# screwshield-v1_0.net
KiCad netlist of a schematic drawn in EAGLE
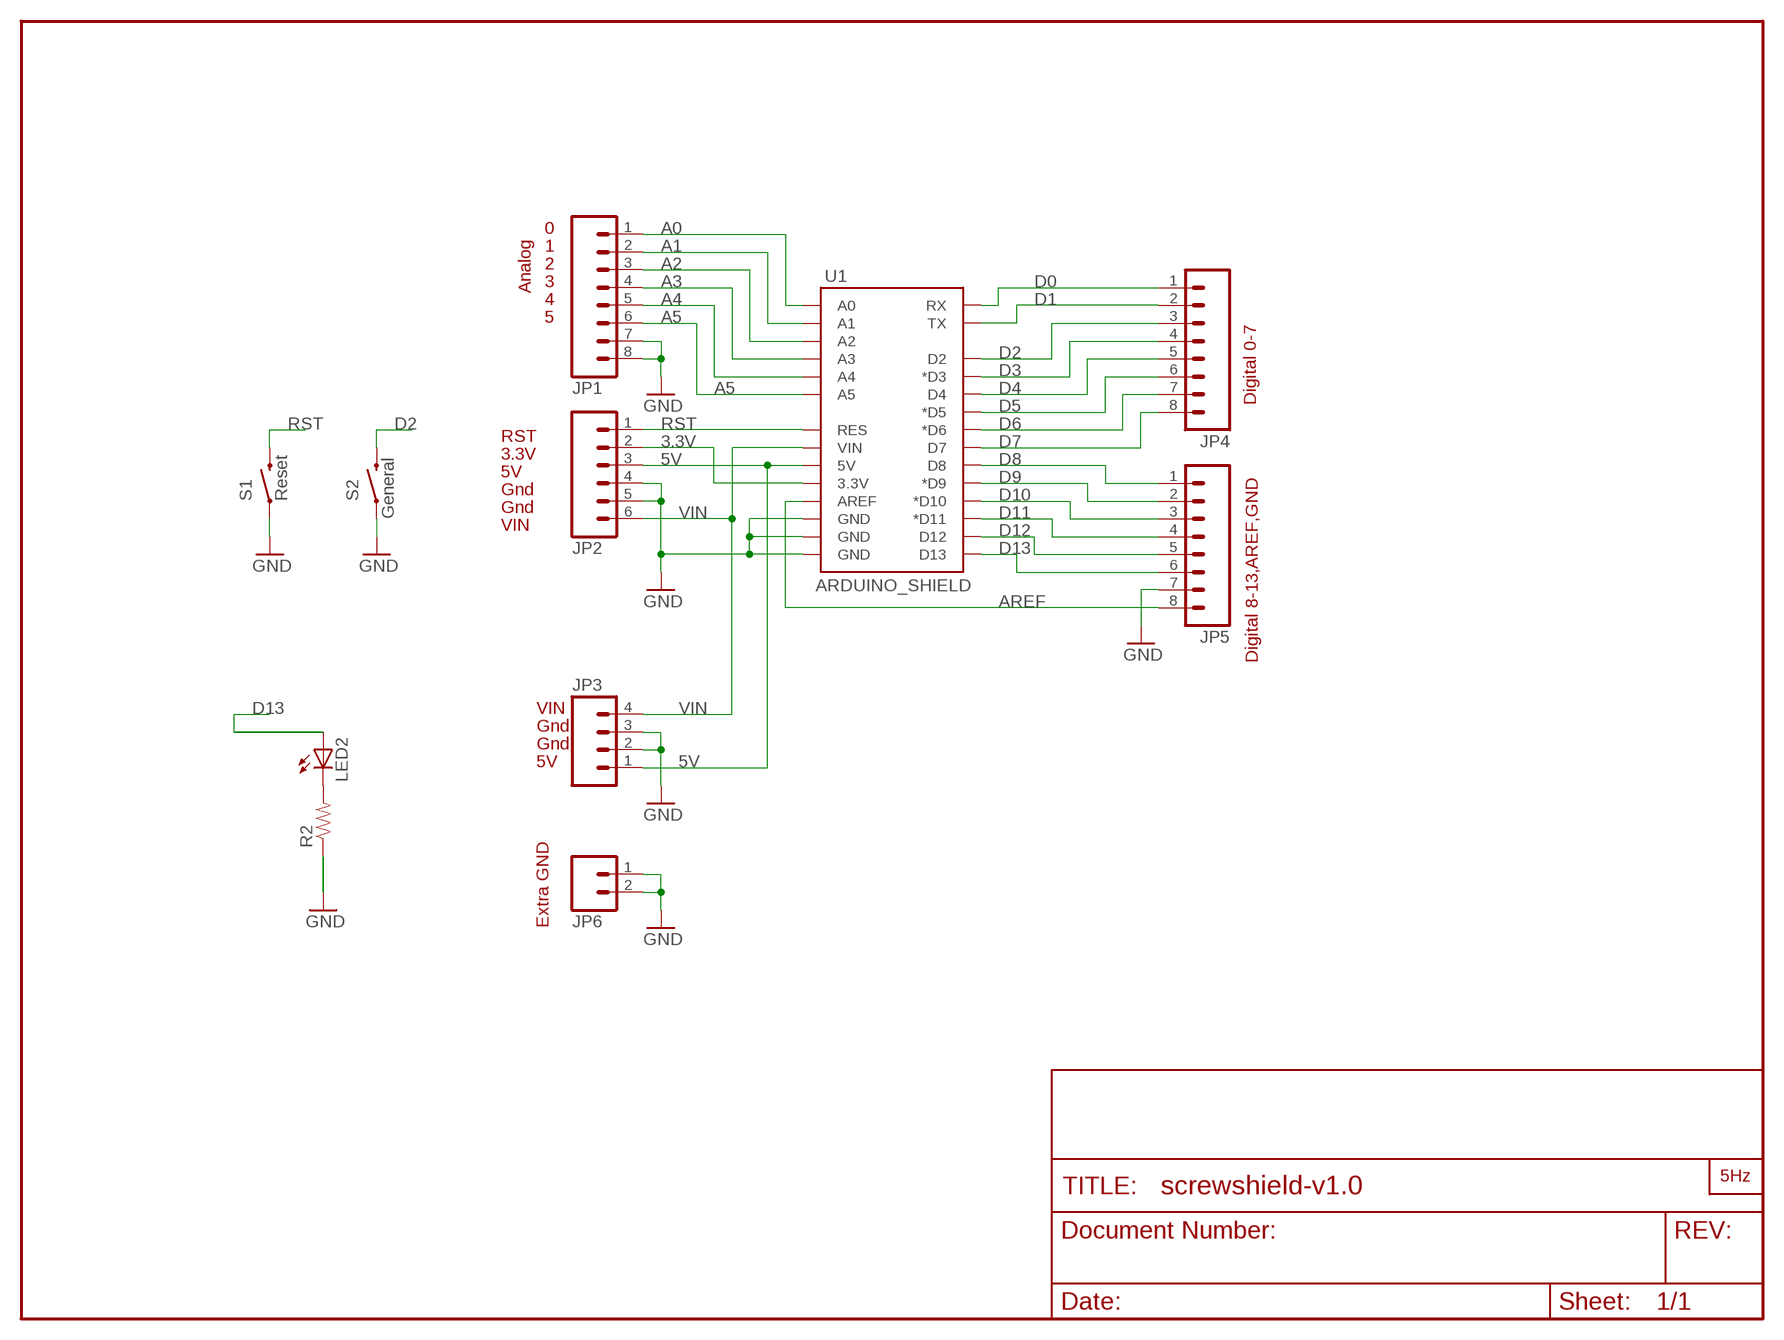
[diagram p0: schematic, sheet 1]

(export (version "E")
  (design (tool "Eeschema 10.0.6"))
  (components
    (comp (ref "JP1")
      (value "M083.5MM-8")
      (footprint "eagle-import:SCREWTERMINAL-3.5MM-8")
      (libsource (lib "eagle-import") (part "M083.5MM-8"))
    )
    (comp (ref "JP2")
      (value "M063.5MM-6")
      (footprint "eagle-import:SCREWTERMINAL-3.5MM-6")
      (libsource (lib "eagle-import") (part "M063.5MM-6"))
    )
    (comp (ref "JP3")
      (value "M04SCREW")
      (footprint "eagle-import:SCREWTERMINAL-3.5MM-4")
      (libsource (lib "eagle-import") (part "M04SCREW"))
    )
    (comp (ref "JP4")
      (value "M083.5MM-8")
      (footprint "eagle-import:SCREWTERMINAL-3.5MM-8")
      (libsource (lib "eagle-import") (part "M083.5MM-8"))
    )
    (comp (ref "JP5")
      (value "M083.5MM-8")
      (footprint "eagle-import:SCREWTERMINAL-3.5MM-8")
      (libsource (lib "eagle-import") (part "M083.5MM-8"))
    )
    (comp (ref "JP6")
      (value "M023.5MM")
      (footprint "eagle-import:SCREWTERMINAL-3.5MM-2")
      (libsource (lib "eagle-import") (part "M023.5MM"))
    )
    (comp (ref "LED2")
      (value "LED0603")
      (footprint "eagle-import:LED-0603")
      (libsource (lib "eagle-import") (part "LED0603"))
    )
    (comp (ref "R2")
      (value "RESISTOR0603-RES")
      (footprint "eagle-import:0603-RES")
      (libsource (lib "eagle-import") (part "RESISTOR0603-RES"))
    )
    (comp (ref "S1")
      (value "Reset")
      (footprint "eagle-import:TACTILE-PTH")
      (libsource (lib "eagle-import") (part "SWITCH-MOMENTARY-2PTH"))
    )
    (comp (ref "S2")
      (value "General")
      (footprint "eagle-import:TACTILE-PTH")
      (libsource (lib "eagle-import") (part "SWITCH-MOMENTARY-2PTH"))
    )
    (comp (ref "U$1")
      (value "LOGO_SILKL15MM")
      (footprint "eagle-import:LARGO_15MM")
      (libsource (lib "eagle-import") (part "LOGO_SILKL15MM"))
    )
    (comp (ref "U1")
      (value "ARDUINO_SHIELD")
      (footprint "eagle-import:DUEMILANOVE_SHIELD_NOHOLES")
      (libsource (lib "eagle-import") (part "ARDUINO_SHIELDNOHOLES"))
    )
  )
  (nets
    (net (code "1") (name "/3.3V") (class "Default")
      (node (ref "JP2") (pin "2") (pinfunction "2_2") (pintype "passive"))
      (node (ref "U1") (pin "3.3V") (pinfunction "3.3V_3.3V") (pintype "bidirectional"))
    )
    (net (code "2") (name "/5V") (class "Default")
      (node (ref "JP2") (pin "3") (pinfunction "3_3") (pintype "passive"))
      (node (ref "JP3") (pin "1") (pinfunction "1_1") (pintype "passive"))
      (node (ref "U1") (pin "5V") (pinfunction "5V_5V") (pintype "bidirectional"))
    )
    (net (code "3") (name "/A0") (class "Default")
      (node (ref "JP1") (pin "1") (pinfunction "1_1") (pintype "passive"))
      (node (ref "U1") (pin "A0") (pinfunction "A0_A0") (pintype "bidirectional"))
    )
    (net (code "4") (name "/A1") (class "Default")
      (node (ref "JP1") (pin "2") (pinfunction "2_2") (pintype "passive"))
      (node (ref "U1") (pin "A1") (pinfunction "A1_A1") (pintype "bidirectional"))
    )
    (net (code "5") (name "/A2") (class "Default")
      (node (ref "JP1") (pin "3") (pinfunction "3_3") (pintype "passive"))
      (node (ref "U1") (pin "A2") (pinfunction "A2_A2") (pintype "bidirectional"))
    )
    (net (code "6") (name "/A3") (class "Default")
      (node (ref "JP1") (pin "4") (pinfunction "4_4") (pintype "passive"))
      (node (ref "U1") (pin "A3") (pinfunction "A3_A3") (pintype "bidirectional"))
    )
    (net (code "7") (name "/A4") (class "Default")
      (node (ref "JP1") (pin "5") (pinfunction "5_5") (pintype "passive"))
      (node (ref "U1") (pin "A4") (pinfunction "A4_A4") (pintype "bidirectional"))
    )
    (net (code "8") (name "/A5") (class "Default")
      (node (ref "JP1") (pin "6") (pinfunction "6_6") (pintype "passive"))
      (node (ref "U1") (pin "A5") (pinfunction "A5_A5") (pintype "bidirectional"))
    )
    (net (code "9") (name "/AREF") (class "Default")
      (node (ref "JP5") (pin "8") (pinfunction "8_8") (pintype "passive"))
      (node (ref "U1") (pin "AREF") (pinfunction "AREF_AREF") (pintype "bidirectional"))
    )
    (net (code "10") (name "/D0") (class "Default")
      (node (ref "JP4") (pin "1") (pinfunction "1_1") (pintype "passive"))
      (node (ref "U1") (pin "RX") (pinfunction "RX_RX") (pintype "bidirectional"))
    )
    (net (code "11") (name "/D1") (class "Default")
      (node (ref "JP4") (pin "2") (pinfunction "2_2") (pintype "passive"))
      (node (ref "U1") (pin "TX") (pinfunction "TX_TX") (pintype "bidirectional"))
    )
    (net (code "12") (name "/D2") (class "Default")
      (node (ref "JP4") (pin "3") (pinfunction "3_3") (pintype "passive"))
      (node (ref "S2") (pin "3") (pinfunction "2_3") (pintype "passive"))
      (node (ref "U1") (pin "D2") (pinfunction "D2_D2") (pintype "bidirectional"))
    )
    (net (code "13") (name "/D3") (class "Default")
      (node (ref "JP4") (pin "4") (pinfunction "4_4") (pintype "passive"))
      (node (ref "U1") (pin "D3") (pinfunction "*D3_D3") (pintype "bidirectional"))
    )
    (net (code "14") (name "/D4") (class "Default")
      (node (ref "JP4") (pin "5") (pinfunction "5_5") (pintype "passive"))
      (node (ref "U1") (pin "D4") (pinfunction "D4_D4") (pintype "bidirectional"))
    )
    (net (code "15") (name "/D5") (class "Default")
      (node (ref "JP4") (pin "6") (pinfunction "6_6") (pintype "passive"))
      (node (ref "U1") (pin "D5") (pinfunction "*D5_D5") (pintype "bidirectional"))
    )
    (net (code "16") (name "/D6") (class "Default")
      (node (ref "JP4") (pin "7") (pinfunction "7_7") (pintype "passive"))
      (node (ref "U1") (pin "D6") (pinfunction "*D6_D6") (pintype "bidirectional"))
    )
    (net (code "17") (name "/D7") (class "Default")
      (node (ref "JP4") (pin "8") (pinfunction "8_8") (pintype "passive"))
      (node (ref "U1") (pin "D7") (pinfunction "D7_D7") (pintype "bidirectional"))
    )
    (net (code "18") (name "/D8") (class "Default")
      (node (ref "JP5") (pin "1") (pinfunction "1_1") (pintype "passive"))
      (node (ref "U1") (pin "D8") (pinfunction "D8_D8") (pintype "bidirectional"))
    )
    (net (code "19") (name "/D9") (class "Default")
      (node (ref "JP5") (pin "2") (pinfunction "2_2") (pintype "passive"))
      (node (ref "U1") (pin "D9") (pinfunction "*D9_D9") (pintype "bidirectional"))
    )
    (net (code "20") (name "/D10") (class "Default")
      (node (ref "JP5") (pin "3") (pinfunction "3_3") (pintype "passive"))
      (node (ref "U1") (pin "D10") (pinfunction "*D10_D10") (pintype "bidirectional"))
    )
    (net (code "21") (name "/D11") (class "Default")
      (node (ref "JP5") (pin "4") (pinfunction "4_4") (pintype "passive"))
      (node (ref "U1") (pin "D11") (pinfunction "*D11_D11") (pintype "bidirectional"))
    )
    (net (code "22") (name "/D12") (class "Default")
      (node (ref "JP5") (pin "5") (pinfunction "5_5") (pintype "passive"))
      (node (ref "U1") (pin "D12") (pinfunction "D12_D12") (pintype "bidirectional"))
    )
    (net (code "23") (name "/D13") (class "Default")
      (node (ref "JP5") (pin "6") (pinfunction "6_6") (pintype "passive"))
      (node (ref "LED2") (pin "A") (pinfunction "A_A") (pintype "passive"))
      (node (ref "U1") (pin "D13") (pinfunction "D13_D13") (pintype "bidirectional"))
    )
    (net (code "24") (name "/RST") (class "Default")
      (node (ref "JP2") (pin "1") (pinfunction "1_1") (pintype "passive"))
      (node (ref "S1") (pin "3") (pinfunction "2_3") (pintype "passive"))
      (node (ref "U1") (pin "RES") (pinfunction "RES_RES") (pintype "bidirectional"))
    )
    (net (code "25") (name "/VIN") (class "Default")
      (node (ref "JP2") (pin "6") (pinfunction "6_6") (pintype "passive"))
      (node (ref "JP3") (pin "4") (pinfunction "4_4") (pintype "passive"))
      (node (ref "U1") (pin "VIN") (pinfunction "VIN_VIN") (pintype "bidirectional"))
    )
    (net (code "26") (name "GND") (class "Default")
      (node (ref "JP1") (pin "7") (pinfunction "7_7") (pintype "passive"))
      (node (ref "JP1") (pin "8") (pinfunction "8_8") (pintype "passive"))
      (node (ref "JP2") (pin "4") (pinfunction "4_4") (pintype "passive"))
      (node (ref "JP2") (pin "5") (pinfunction "5_5") (pintype "passive"))
      (node (ref "JP3") (pin "2") (pinfunction "2_2") (pintype "passive"))
      (node (ref "JP3") (pin "3") (pinfunction "3_3") (pintype "passive"))
      (node (ref "JP5") (pin "7") (pinfunction "7_7") (pintype "passive"))
      (node (ref "JP6") (pin "1") (pinfunction "1_1") (pintype "passive"))
      (node (ref "JP6") (pin "2") (pinfunction "2_2") (pintype "passive"))
      (node (ref "R2") (pin "1") (pinfunction "1_1") (pintype "passive"))
      (node (ref "S1") (pin "1") (pinfunction "1_1") (pintype "passive"))
      (node (ref "S2") (pin "1") (pinfunction "1_1") (pintype "passive"))
      (node (ref "U1") (pin "GND@0") (pinfunction "GND_GND@0") (pintype "bidirectional"))
      (node (ref "U1") (pin "GND@1") (pinfunction "GND_GND@1") (pintype "bidirectional"))
      (node (ref "U1") (pin "GND@2") (pinfunction "GND_GND@2") (pintype "bidirectional"))
    )
    (net (code "27") (name "Net-(LED2-PadC)") (class "Default")
      (node (ref "LED2") (pin "C") (pinfunction "C_C") (pintype "passive"))
      (node (ref "R2") (pin "2") (pinfunction "2_2") (pintype "passive"))
    )
  )
)
